# Pot4_4_MCP3008.net
KiCad netlist of a schematic drawn in EAGLE
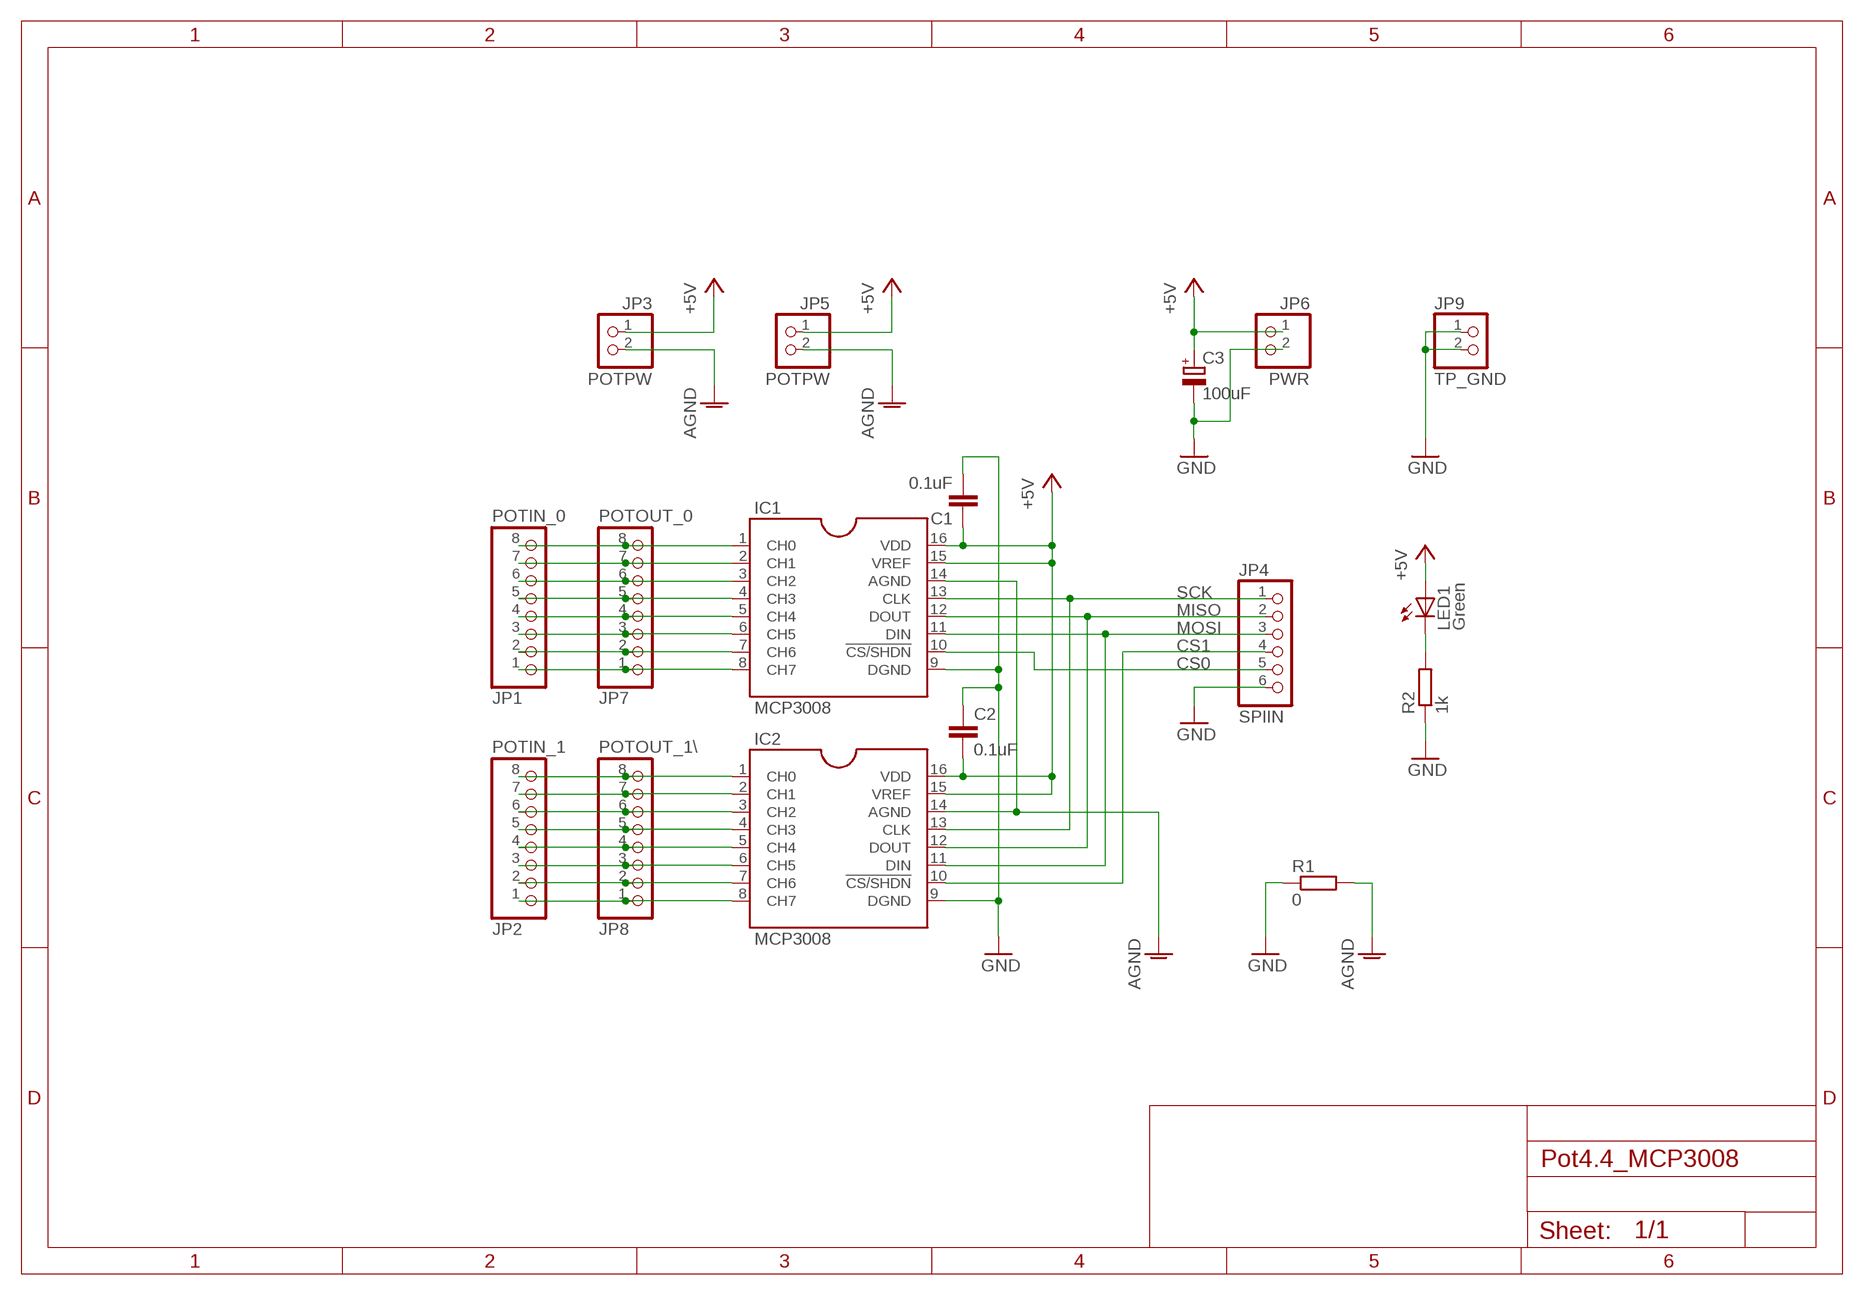
[diagram p0: schematic, sheet 1]

(export (version "E")
  (design (tool "Eeschema 10.0.6"))
  (components
    (comp (ref "C1")
      (value "0.1uF")
      (footprint "eagle-import:C025-024X044")
      (libsource (lib "eagle-import") (part "C-EU025-024X044"))
    )
    (comp (ref "C2")
      (value "0.1uF")
      (footprint "eagle-import:C025-024X044")
      (libsource (lib "eagle-import") (part "C-EU025-024X044"))
    )
    (comp (ref "C3")
      (value "100uF")
      (footprint "eagle-import:SANYO-OSCON_C")
      (libsource (lib "eagle-import") (part "CPOL-EUSANYO_C"))
    )
    (comp (ref "IC1")
      (value "MCP3008")
      (footprint "eagle-import:MCP3008")
      (libsource (lib "eagle-import") (part "MCP3008"))
    )
    (comp (ref "IC2")
      (value "MCP3008")
      (footprint "eagle-import:MCP3008")
      (libsource (lib "eagle-import") (part "MCP3008"))
    )
    (comp (ref "JP1")
      (value "POTIN_0")
      (footprint "eagle-import:1X08_90")
      (libsource (lib "eagle-import") (part "PINHD-1X8/90"))
    )
    (comp (ref "JP2")
      (value "POTIN_1")
      (footprint "eagle-import:1X08_90")
      (libsource (lib "eagle-import") (part "PINHD-1X8/90"))
    )
    (comp (ref "JP3")
      (value "POTPW")
      (footprint "eagle-import:1X02_90")
      (libsource (lib "eagle-import") (part "PINHD-1X2/90"))
    )
    (comp (ref "JP4")
      (value "SPIIN")
      (footprint "eagle-import:1X06_90")
      (libsource (lib "eagle-import") (part "PINHD-1X6/90"))
    )
    (comp (ref "JP5")
      (value "POTPW")
      (footprint "eagle-import:1X02_90")
      (libsource (lib "eagle-import") (part "PINHD-1X2/90"))
    )
    (comp (ref "JP6")
      (value "PWR")
      (footprint "eagle-import:1X02_90")
      (libsource (lib "eagle-import") (part "PINHD-1X2/90"))
    )
    (comp (ref "JP7")
      (value "POTOUT_0")
      (footprint "eagle-import:1X08")
      (libsource (lib "eagle-import") (part "PINHD-1X8"))
    )
    (comp (ref "JP8")
      (value "POTOUT_1\\")
      (footprint "eagle-import:1X08")
      (libsource (lib "eagle-import") (part "PINHD-1X8"))
    )
    (comp (ref "JP9")
      (value "TP_GND")
      (footprint "eagle-import:1X02")
      (libsource (lib "eagle-import") (part "PINHD-1X2"))
    )
    (comp (ref "LED1")
      (value "Green")
      (footprint "eagle-import:LED3MM")
      (libsource (lib "eagle-import") (part "LED3MM"))
    )
    (comp (ref "R1")
      (value "0")
      (footprint "eagle-import:0204V")
      (libsource (lib "eagle-import") (part "R-EU_0204/2V"))
    )
    (comp (ref "R2")
      (value "1k")
      (footprint "eagle-import:0207_7")
      (libsource (lib "eagle-import") (part "R-EU_0207/7"))
    )
  )
  (nets
    (net (code "1") (name "+5V") (class "Default")
      (node (ref "C1") (pin "1") (pinfunction "1_1") (pintype "passive"))
      (node (ref "C2") (pin "2") (pinfunction "2_2") (pintype "passive"))
      (node (ref "C3") (pin "+") (pinfunction "+_+") (pintype "passive"))
      (node (ref "IC1") (pin "15") (pinfunction "VREF_15") (pintype "passive"))
      (node (ref "IC1") (pin "16") (pinfunction "VDD_16") (pintype "passive"))
      (node (ref "IC2") (pin "15") (pinfunction "VREF_15") (pintype "passive"))
      (node (ref "IC2") (pin "16") (pinfunction "VDD_16") (pintype "passive"))
      (node (ref "JP3") (pin "1") (pinfunction "1_1") (pintype "passive"))
      (node (ref "JP5") (pin "1") (pinfunction "1_1") (pintype "passive"))
      (node (ref "JP6") (pin "1") (pinfunction "1_1") (pintype "passive"))
      (node (ref "LED1") (pin "A") (pinfunction "A_A") (pintype "passive"))
    )
    (net (code "2") (name "/CS0") (class "Default")
      (node (ref "IC1") (pin "10") (pinfunction "~{CS/SHDN}_10") (pintype "passive"))
      (node (ref "JP4") (pin "5") (pinfunction "5_5") (pintype "passive"))
    )
    (net (code "3") (name "/CS1") (class "Default")
      (node (ref "IC2") (pin "10") (pinfunction "~{CS/SHDN}_10") (pintype "passive"))
      (node (ref "JP4") (pin "4") (pinfunction "4_4") (pintype "passive"))
    )
    (net (code "4") (name "/MISO") (class "Default")
      (node (ref "IC1") (pin "12") (pinfunction "DOUT_12") (pintype "passive"))
      (node (ref "IC2") (pin "12") (pinfunction "DOUT_12") (pintype "passive"))
      (node (ref "JP4") (pin "2") (pinfunction "2_2") (pintype "passive"))
    )
    (net (code "5") (name "/MOSI") (class "Default")
      (node (ref "IC1") (pin "11") (pinfunction "DIN_11") (pintype "passive"))
      (node (ref "IC2") (pin "11") (pinfunction "DIN_11") (pintype "passive"))
      (node (ref "JP4") (pin "3") (pinfunction "3_3") (pintype "passive"))
    )
    (net (code "6") (name "/SCK") (class "Default")
      (node (ref "IC1") (pin "13") (pinfunction "CLK_13") (pintype "passive"))
      (node (ref "IC2") (pin "13") (pinfunction "CLK_13") (pintype "passive"))
      (node (ref "JP4") (pin "1") (pinfunction "1_1") (pintype "passive"))
    )
    (net (code "7") (name "AGND") (class "Default")
      (node (ref "IC1") (pin "14") (pinfunction "AGND_14") (pintype "passive"))
      (node (ref "IC2") (pin "14") (pinfunction "AGND_14") (pintype "passive"))
      (node (ref "JP3") (pin "2") (pinfunction "2_2") (pintype "passive"))
      (node (ref "JP5") (pin "2") (pinfunction "2_2") (pintype "passive"))
      (node (ref "R1") (pin "2") (pinfunction "2_2") (pintype "passive"))
    )
    (net (code "8") (name "GND") (class "Default")
      (node (ref "C1") (pin "2") (pinfunction "2_2") (pintype "passive"))
      (node (ref "C2") (pin "1") (pinfunction "1_1") (pintype "passive"))
      (node (ref "C3") (pin "-") (pinfunction "-_-") (pintype "passive"))
      (node (ref "IC1") (pin "9") (pinfunction "DGND_9") (pintype "passive"))
      (node (ref "IC2") (pin "9") (pinfunction "DGND_9") (pintype "passive"))
      (node (ref "JP4") (pin "6") (pinfunction "6_6") (pintype "passive"))
      (node (ref "JP6") (pin "2") (pinfunction "2_2") (pintype "passive"))
      (node (ref "JP9") (pin "1") (pinfunction "1_1") (pintype "passive"))
      (node (ref "JP9") (pin "2") (pinfunction "2_2") (pintype "passive"))
      (node (ref "R1") (pin "1") (pinfunction "1_1") (pintype "passive"))
      (node (ref "R2") (pin "1") (pinfunction "1_1") (pintype "passive"))
    )
    (net (code "9") (name "Net-(IC1-CH0)") (class "Default")
      (node (ref "IC1") (pin "1") (pinfunction "CH0_1") (pintype "passive"))
      (node (ref "JP1") (pin "8") (pinfunction "8_8") (pintype "passive"))
      (node (ref "JP7") (pin "8") (pinfunction "8_8") (pintype "passive"))
    )
    (net (code "10") (name "Net-(IC1-CH1)") (class "Default")
      (node (ref "IC1") (pin "2") (pinfunction "CH1_2") (pintype "passive"))
      (node (ref "JP1") (pin "7") (pinfunction "7_7") (pintype "passive"))
      (node (ref "JP7") (pin "7") (pinfunction "7_7") (pintype "passive"))
    )
    (net (code "11") (name "Net-(IC1-CH2)") (class "Default")
      (node (ref "IC1") (pin "3") (pinfunction "CH2_3") (pintype "passive"))
      (node (ref "JP1") (pin "6") (pinfunction "6_6") (pintype "passive"))
      (node (ref "JP7") (pin "6") (pinfunction "6_6") (pintype "passive"))
    )
    (net (code "12") (name "Net-(IC1-CH3)") (class "Default")
      (node (ref "IC1") (pin "4") (pinfunction "CH3_4") (pintype "passive"))
      (node (ref "JP1") (pin "5") (pinfunction "5_5") (pintype "passive"))
      (node (ref "JP7") (pin "5") (pinfunction "5_5") (pintype "passive"))
    )
    (net (code "13") (name "Net-(IC1-CH4)") (class "Default")
      (node (ref "IC1") (pin "5") (pinfunction "CH4_5") (pintype "passive"))
      (node (ref "JP1") (pin "4") (pinfunction "4_4") (pintype "passive"))
      (node (ref "JP7") (pin "4") (pinfunction "4_4") (pintype "passive"))
    )
    (net (code "14") (name "Net-(IC1-CH5)") (class "Default")
      (node (ref "IC1") (pin "6") (pinfunction "CH5_6") (pintype "passive"))
      (node (ref "JP1") (pin "3") (pinfunction "3_3") (pintype "passive"))
      (node (ref "JP7") (pin "3") (pinfunction "3_3") (pintype "passive"))
    )
    (net (code "15") (name "Net-(IC1-CH6)") (class "Default")
      (node (ref "IC1") (pin "7") (pinfunction "CH6_7") (pintype "passive"))
      (node (ref "JP1") (pin "2") (pinfunction "2_2") (pintype "passive"))
      (node (ref "JP7") (pin "2") (pinfunction "2_2") (pintype "passive"))
    )
    (net (code "16") (name "Net-(IC1-CH7)") (class "Default")
      (node (ref "IC1") (pin "8") (pinfunction "CH7_8") (pintype "passive"))
      (node (ref "JP1") (pin "1") (pinfunction "1_1") (pintype "passive"))
      (node (ref "JP7") (pin "1") (pinfunction "1_1") (pintype "passive"))
    )
    (net (code "17") (name "Net-(IC2-CH0)") (class "Default")
      (node (ref "IC2") (pin "1") (pinfunction "CH0_1") (pintype "passive"))
      (node (ref "JP2") (pin "8") (pinfunction "8_8") (pintype "passive"))
      (node (ref "JP8") (pin "8") (pinfunction "8_8") (pintype "passive"))
    )
    (net (code "18") (name "Net-(IC2-CH1)") (class "Default")
      (node (ref "IC2") (pin "2") (pinfunction "CH1_2") (pintype "passive"))
      (node (ref "JP2") (pin "7") (pinfunction "7_7") (pintype "passive"))
      (node (ref "JP8") (pin "7") (pinfunction "7_7") (pintype "passive"))
    )
    (net (code "19") (name "Net-(IC2-CH2)") (class "Default")
      (node (ref "IC2") (pin "3") (pinfunction "CH2_3") (pintype "passive"))
      (node (ref "JP2") (pin "6") (pinfunction "6_6") (pintype "passive"))
      (node (ref "JP8") (pin "6") (pinfunction "6_6") (pintype "passive"))
    )
    (net (code "20") (name "Net-(IC2-CH3)") (class "Default")
      (node (ref "IC2") (pin "4") (pinfunction "CH3_4") (pintype "passive"))
      (node (ref "JP2") (pin "5") (pinfunction "5_5") (pintype "passive"))
      (node (ref "JP8") (pin "5") (pinfunction "5_5") (pintype "passive"))
    )
    (net (code "21") (name "Net-(IC2-CH4)") (class "Default")
      (node (ref "IC2") (pin "5") (pinfunction "CH4_5") (pintype "passive"))
      (node (ref "JP2") (pin "4") (pinfunction "4_4") (pintype "passive"))
      (node (ref "JP8") (pin "4") (pinfunction "4_4") (pintype "passive"))
    )
    (net (code "22") (name "Net-(IC2-CH5)") (class "Default")
      (node (ref "IC2") (pin "6") (pinfunction "CH5_6") (pintype "passive"))
      (node (ref "JP2") (pin "3") (pinfunction "3_3") (pintype "passive"))
      (node (ref "JP8") (pin "3") (pinfunction "3_3") (pintype "passive"))
    )
    (net (code "23") (name "Net-(IC2-CH6)") (class "Default")
      (node (ref "IC2") (pin "7") (pinfunction "CH6_7") (pintype "passive"))
      (node (ref "JP2") (pin "2") (pinfunction "2_2") (pintype "passive"))
      (node (ref "JP8") (pin "2") (pinfunction "2_2") (pintype "passive"))
    )
    (net (code "24") (name "Net-(IC2-CH7)") (class "Default")
      (node (ref "IC2") (pin "8") (pinfunction "CH7_8") (pintype "passive"))
      (node (ref "JP2") (pin "1") (pinfunction "1_1") (pintype "passive"))
      (node (ref "JP8") (pin "1") (pinfunction "1_1") (pintype "passive"))
    )
    (net (code "25") (name "Net-(LED1-C)") (class "Default")
      (node (ref "LED1") (pin "K") (pinfunction "C_K") (pintype "passive"))
      (node (ref "R2") (pin "2") (pinfunction "2_2") (pintype "passive"))
    )
  )
)
